# FAN_Conn.net
KiCad netlist of a schematic drawn in Altium Designer
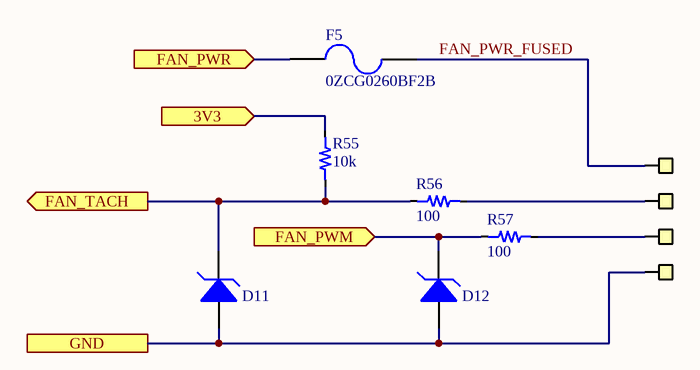
[diagram p0: FAN_Conn.SchDoc]

(export (version "E")
  (design (tool "Eeschema 10.0.6"))
  (components
    (comp (ref "D11")
      (value "SZMMSZ5227BT1G")
      (footprint "SOD-123")
      (description "Zener Diode 3.6 V 500 mW ±5% Surface Mount SOD-123")
      (libsource (lib "Diodes") (part "SZMMSZ5227BT1G"))
    )
    (comp (ref "D12")
      (value "SZMMSZ5227BT1G")
      (footprint "SOD-123")
      (description "Zener Diode 3.6 V 500 mW ±5% Surface Mount SOD-123")
      (libsource (lib "Diodes") (part "SZMMSZ5227BT1G"))
    )
    (comp (ref "F5")
      (value "0ZCG0260BF2B")
      (footprint "1812_PTC_FUSE")
      (description "Generic PTC fuse footprints. Add")
      (libsource (lib "Fuses") (part "PTC Fuse"))
    )
    (comp (ref "R55")
      (value "10k")
      (footprint "0603_RES")
      (fields (field (name "Comment") "Resistor"))
      (libsource (lib "Resistors") (part "Resistor"))
    )
    (comp (ref "R56")
      (value "100")
      (footprint "0603_RES")
      (fields (field (name "Comment") "Resistor"))
      (libsource (lib "Resistors") (part "Resistor"))
    )
    (comp (ref "R57")
      (value "100")
      (footprint "0603_RES")
      (fields (field (name "Comment") "Resistor"))
      (libsource (lib "Resistors") (part "Resistor"))
    )
    (comp (ref "X6")
      (value "GenericPinHeader(0.1in)")
      (footprint "GenericPinHeader(.1in)")
      (description "Generic .1in(2.54mm) pitch pin header")
      (libsource (lib "Connectors") (part "GenericPinHeader(0.1in)"))
    )
    (comp (ref "X7")
      (value "GenericPinHeader(0.1in)")
      (footprint "GenericPinHeader(.1in)")
      (description "Generic .1in(2.54mm) pitch pin header")
      (libsource (lib "Connectors") (part "GenericPinHeader(0.1in)"))
    )
    (comp (ref "X8")
      (value "GenericPinHeader(0.1in)")
      (footprint "GenericPinHeader(.1in)")
      (description "Generic .1in(2.54mm) pitch pin header")
      (libsource (lib "Connectors") (part "GenericPinHeader(0.1in)"))
    )
    (comp (ref "X9")
      (value "GenericPinHeader(0.1in)")
      (footprint "GenericPinHeader(.1in)")
      (description "Generic .1in(2.54mm) pitch pin header")
      (libsource (lib "Connectors") (part "GenericPinHeader(0.1in)"))
    )
  )
  (nets
    (net (code "1") (name "/3V3") (class "Default")
      (node (ref "R55") (pin "2") (pinfunction "2_2") (pintype "passive"))
    )
    (net (code "2") (name "/FAN_PWM") (class "Default")
      (node (ref "D12") (pin "1") (pinfunction "K_1") (pintype "passive"))
      (node (ref "R57") (pin "2") (pinfunction "2_2") (pintype "passive"))
    )
    (net (code "3") (name "/FAN_PWR") (class "Default")
      (node (ref "F5") (pin "1") (pinfunction "1_1") (pintype "passive"))
    )
    (net (code "4") (name "/FAN_PWR_FUSED") (class "Default")
      (node (ref "F5") (pin "2") (pinfunction "2_2") (pintype "passive"))
      (node (ref "X6") (pin "1") (pinfunction "Pin_1") (pintype "passive"))
    )
    (net (code "5") (name "/FAN_TACH") (class "Default")
      (node (ref "D11") (pin "1") (pinfunction "K_1") (pintype "passive"))
      (node (ref "R55") (pin "1") (pinfunction "1_1") (pintype "passive"))
      (node (ref "R56") (pin "2") (pinfunction "2_2") (pintype "passive"))
    )
    (net (code "6") (name "/GND") (class "Default")
      (node (ref "D11") (pin "2") (pinfunction "A_2") (pintype "passive"))
      (node (ref "D12") (pin "2") (pinfunction "A_2") (pintype "passive"))
      (node (ref "X9") (pin "1") (pinfunction "Pin_1") (pintype "passive"))
    )
    (net (code "7") (name "Net-(X7-Pin)") (class "Default")
      (node (ref "R56") (pin "1") (pinfunction "1_1") (pintype "passive"))
      (node (ref "X7") (pin "1") (pinfunction "Pin_1") (pintype "passive"))
    )
    (net (code "8") (name "Net-(X8-Pin)") (class "Default")
      (node (ref "R57") (pin "1") (pinfunction "1_1") (pintype "passive"))
      (node (ref "X8") (pin "1") (pinfunction "Pin_1") (pintype "passive"))
    )
  )
)
